# apu_mega_shield.net
KiCad netlist of a schematic drawn in EAGLE
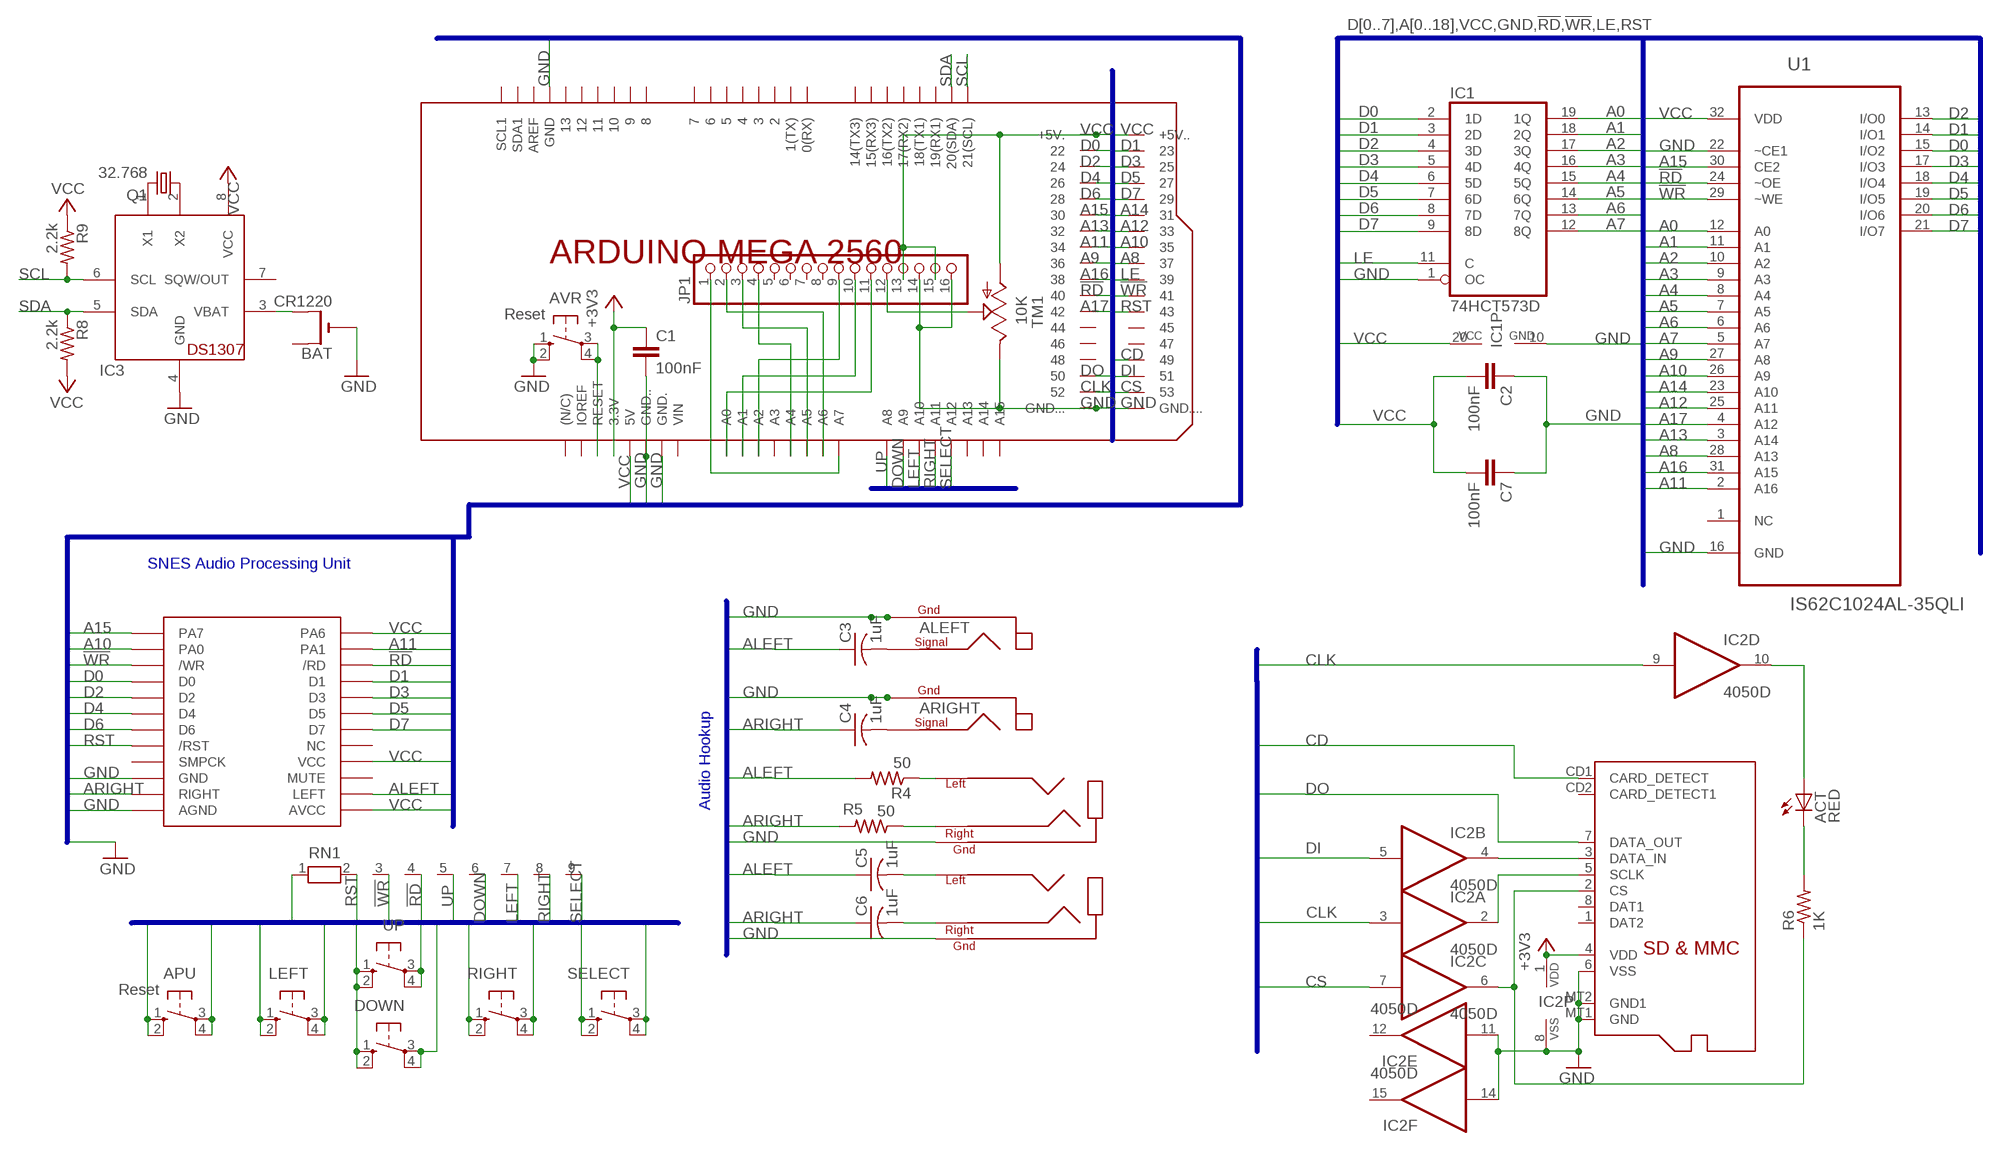
[diagram p0: schematic, sheet 1]

(export (version "E")
  (design (tool "Eeschema 10.0.6"))
  (components
    (comp (ref "ACT")
      (value "RED")
      (footprint "eagle-import:CHIP-LED0805")
      (libsource (lib "eagle-import") (part "LEDCHIP-LED0805"))
    )
    (comp (ref "APU")
      (value "Reset")
      (footprint "eagle-import:B3F-10XX")
      (libsource (lib "eagle-import") (part "10-XX"))
    )
    (comp (ref "AVR")
      (value "Reset")
      (footprint "eagle-import:B3F-10XX")
      (libsource (lib "eagle-import") (part "10-XX"))
    )
    (comp (ref "BAT")
      (value "CR1220")
      (footprint "eagle-import:CR1220-THM")
      (libsource (lib "eagle-import") (part "CR1220THM"))
    )
    (comp (ref "C1")
      (value "100nF")
      (footprint "eagle-import:C0603")
      (libsource (lib "eagle-import") (part "C-EUC0603"))
    )
    (comp (ref "C2")
      (value "100nF")
      (footprint "eagle-import:C0603")
      (libsource (lib "eagle-import") (part "C-EUC0603"))
    )
    (comp (ref "C3")
      (value "1uF")
      (footprint "eagle-import:C025-025X050")
      (libsource (lib "eagle-import") (part "C-US025-025X050"))
    )
    (comp (ref "C4")
      (value "1uF")
      (footprint "eagle-import:C025-025X050")
      (libsource (lib "eagle-import") (part "C-US025-025X050"))
    )
    (comp (ref "C5")
      (value "1uF")
      (footprint "eagle-import:C025-025X050")
      (libsource (lib "eagle-import") (part "C-US025-025X050"))
    )
    (comp (ref "C6")
      (value "1uF")
      (footprint "eagle-import:C025-025X050")
      (libsource (lib "eagle-import") (part "C-US025-025X050"))
    )
    (comp (ref "C7")
      (value "100nF")
      (footprint "eagle-import:C0603")
      (libsource (lib "eagle-import") (part "C-EUC0603"))
    )
    (comp (ref "DOWN")
      (value "10-XX")
      (footprint "eagle-import:B3F-10XX")
      (libsource (lib "eagle-import") (part "10-XX"))
    )
    (comp (ref "IC1")
      (value "74HCT573D")
      (footprint "eagle-import:SO20W")
      (libsource (lib "eagle-import") (part "74573DHCT"))
    )
    (comp (ref "IC2")
      (value "4050D")
      (footprint "eagle-import:SO16")
      (libsource (lib "eagle-import") (part "4050D"))
    )
    (comp (ref "IC3")
      (value "DS1307")
      (footprint "eagle-import:DIL08")
      (libsource (lib "eagle-import") (part "DS1307"))
    )
    (comp (ref "JP1")
      (value "PINHD-1X16")
      (footprint "eagle-import:1X16")
      (libsource (lib "eagle-import") (part "PINHD-1X16"))
    )
    (comp (ref "LEFT")
      (value "10-XX")
      (footprint "eagle-import:B3F-10XX")
      (libsource (lib "eagle-import") (part "10-XX"))
    )
    (comp (ref "Q1")
      (value "32.768")
      (footprint "eagle-import:TC38H")
      (libsource (lib "eagle-import") (part "CRYTALTC38H"))
    )
    (comp (ref "R4")
      (value "50")
      (footprint "eagle-import:0207_10")
      (libsource (lib "eagle-import") (part "rcl_R-US_0207/10"))
    )
    (comp (ref "R5")
      (value "50")
      (footprint "eagle-import:0207_10")
      (libsource (lib "eagle-import") (part "rcl_R-US_0207/10"))
    )
    (comp (ref "R6")
      (value "1K")
      (footprint "eagle-import:R0805")
      (libsource (lib "eagle-import") (part "R-US_R0805"))
    )
    (comp (ref "R8")
      (value "2.2k")
      (footprint "eagle-import:0207_10")
      (libsource (lib "eagle-import") (part "R-US_0207/10"))
    )
    (comp (ref "R9")
      (value "2.2k")
      (footprint "eagle-import:0207_10")
      (libsource (lib "eagle-import") (part "R-US_0207/10"))
    )
    (comp (ref "RIGHT")
      (value "10-XX")
      (footprint "eagle-import:B3F-10XX")
      (libsource (lib "eagle-import") (part "10-XX"))
    )
    (comp (ref "RN1")
      (value "RN08")
      (footprint "eagle-import:RN-9")
      (libsource (lib "eagle-import") (part "RN08"))
    )
    (comp (ref "SELECT")
      (value "10-XX")
      (footprint "eagle-import:B3F-10XX")
      (libsource (lib "eagle-import") (part "10-XX"))
    )
    (comp (ref "TM1")
      (value "10K")
      (footprint "eagle-import:CA6H")
      (libsource (lib "eagle-import") (part "TRIM_US-CA6H"))
    )
    (comp (ref "U$1")
      (value "APU")
      (footprint "eagle-import:APU")
      (libsource (lib "eagle-import") (part "APU"))
    )
    (comp (ref "U$2")
      (value "HEADPHONE")
      (footprint "eagle-import:SJ1-3533N")
      (libsource (lib "eagle-import") (part "HEADPHONE"))
    )
    (comp (ref "U$3")
      (value "HEADPHONE")
      (footprint "eagle-import:SJ1-3533N")
      (libsource (lib "eagle-import") (part "HEADPHONE"))
    )
    (comp (ref "U$4")
      (value "RCA")
      (footprint "eagle-import:RCJ-01X")
      (libsource (lib "eagle-import") (part "RCA"))
    )
    (comp (ref "U$5")
      (value "RCA")
      (footprint "eagle-import:RCJ-01X")
      (libsource (lib "eagle-import") (part "RCA"))
    )
    (comp (ref "U$6")
      (value "ARDUINO_MEGA_2560_LITENO_LABELS")
      (footprint "eagle-import:ARDUINO_MEGA2560_LITE_NO_LABELS")
      (libsource (lib "eagle-import") (part "ARDUINO_MEGA_2560_LITENO_LABELS"))
    )
    (comp (ref "U1")
      (value "IS62C1024AL-35QLI")
      (footprint "eagle-import:SOIC127P1412X305-32N")
      (libsource (lib "eagle-import") (part "IS62C1024AL-35QLI"))
    )
    (comp (ref "UP")
      (value "10-XX")
      (footprint "eagle-import:B3F-10XX")
      (libsource (lib "eagle-import") (part "10-XX"))
    )
    (comp (ref "X1")
      (value "MICROSD")
      (footprint "eagle-import:MICROSD")
      (libsource (lib "eagle-import") (part "MICROSD"))
    )
  )
  (nets
    (net (code "1") (name "+3V3") (class "Default")
      (node (ref "C1") (pin "1") (pinfunction "1_1") (pintype "passive"))
      (node (ref "IC2") (pin "1") (pinfunction "VDD_1") (pintype "power_in"))
      (node (ref "U$6") (pin "3.3V") (pinfunction "3.3V_3.3V") (pintype "bidirectional"))
      (node (ref "X1") (pin "4") (pinfunction "VDD_4") (pintype "power_in"))
    )
    (net (code "2") (name "/A0") (class "Default")
      (node (ref "IC1") (pin "19") (pinfunction "1Q_19") (pintype "tri_state"))
      (node (ref "U1") (pin "12") (pinfunction "A0_12") (pintype "input"))
    )
    (net (code "3") (name "/A1") (class "Default")
      (node (ref "IC1") (pin "18") (pinfunction "2Q_18") (pintype "tri_state"))
      (node (ref "U1") (pin "11") (pinfunction "A1_11") (pintype "input"))
    )
    (net (code "4") (name "/A2") (class "Default")
      (node (ref "IC1") (pin "17") (pinfunction "3Q_17") (pintype "tri_state"))
      (node (ref "U1") (pin "10") (pinfunction "A2_10") (pintype "input"))
    )
    (net (code "5") (name "/A3") (class "Default")
      (node (ref "IC1") (pin "16") (pinfunction "4Q_16") (pintype "tri_state"))
      (node (ref "U1") (pin "9") (pinfunction "A3_9") (pintype "input"))
    )
    (net (code "6") (name "/A4") (class "Default")
      (node (ref "IC1") (pin "15") (pinfunction "5Q_15") (pintype "tri_state"))
      (node (ref "U1") (pin "8") (pinfunction "A4_8") (pintype "input"))
    )
    (net (code "7") (name "/A5") (class "Default")
      (node (ref "IC1") (pin "14") (pinfunction "6Q_14") (pintype "tri_state"))
      (node (ref "U1") (pin "7") (pinfunction "A5_7") (pintype "input"))
    )
    (net (code "8") (name "/A6") (class "Default")
      (node (ref "IC1") (pin "13") (pinfunction "7Q_13") (pintype "tri_state"))
      (node (ref "U1") (pin "6") (pinfunction "A6_6") (pintype "input"))
    )
    (net (code "9") (name "/A7") (class "Default")
      (node (ref "IC1") (pin "12") (pinfunction "8Q_12") (pintype "tri_state"))
      (node (ref "U1") (pin "5") (pinfunction "A7_5") (pintype "input"))
    )
    (net (code "10") (name "/A8") (class "Default")
      (node (ref "U$6") (pin "37") (pinfunction "37_37") (pintype "bidirectional"))
      (node (ref "U1") (pin "28") (pinfunction "A13_28") (pintype "input"))
    )
    (net (code "11") (name "/A9") (class "Default")
      (node (ref "U$6") (pin "36") (pinfunction "36_36") (pintype "bidirectional"))
      (node (ref "U1") (pin "27") (pinfunction "A8_27") (pintype "input"))
    )
    (net (code "12") (name "/A10") (class "Default")
      (node (ref "U$1") (pin "P$3") (pinfunction "PA0_P$3") (pintype "bidirectional"))
      (node (ref "U$6") (pin "35") (pinfunction "35_35") (pintype "bidirectional"))
      (node (ref "U1") (pin "26") (pinfunction "A9_26") (pintype "input"))
    )
    (net (code "13") (name "/A11") (class "Default")
      (node (ref "U$1") (pin "P$4") (pinfunction "PA1_P$4") (pintype "bidirectional"))
      (node (ref "U$6") (pin "34") (pinfunction "34_34") (pintype "bidirectional"))
      (node (ref "U1") (pin "2") (pinfunction "A16_2") (pintype "input"))
    )
    (net (code "14") (name "/A12") (class "Default")
      (node (ref "U$6") (pin "33") (pinfunction "33_33") (pintype "bidirectional"))
      (node (ref "U1") (pin "25") (pinfunction "A11_25") (pintype "input"))
    )
    (net (code "15") (name "/A13") (class "Default")
      (node (ref "U$6") (pin "32") (pinfunction "32_32") (pintype "bidirectional"))
      (node (ref "U1") (pin "3") (pinfunction "A14_3") (pintype "input"))
    )
    (net (code "16") (name "/A14") (class "Default")
      (node (ref "U$6") (pin "31") (pinfunction "31_31") (pintype "bidirectional"))
      (node (ref "U1") (pin "23") (pinfunction "A10_23") (pintype "input"))
    )
    (net (code "17") (name "/A15") (class "Default")
      (node (ref "U$1") (pin "P$1") (pinfunction "PA7_P$1") (pintype "bidirectional"))
      (node (ref "U$6") (pin "30") (pinfunction "30_30") (pintype "bidirectional"))
      (node (ref "U1") (pin "30") (pinfunction "CE2_30") (pintype "input"))
    )
    (net (code "18") (name "/A16") (class "Default")
      (node (ref "U$6") (pin "38") (pinfunction "38_38") (pintype "bidirectional"))
      (node (ref "U1") (pin "31") (pinfunction "A15_31") (pintype "input"))
    )
    (net (code "19") (name "/A17") (class "Default")
      (node (ref "U$6") (pin "42") (pinfunction "42_42") (pintype "bidirectional"))
      (node (ref "U1") (pin "4") (pinfunction "A12_4") (pintype "input"))
    )
    (net (code "20") (name "/ALEFT") (class "Default")
      (node (ref "C3") (pin "1") (pinfunction "1_1") (pintype "passive"))
      (node (ref "C5") (pin "1") (pinfunction "1_1") (pintype "passive"))
      (node (ref "R4") (pin "2") (pinfunction "2_2") (pintype "passive"))
      (node (ref "U$1") (pin "P$22") (pinfunction "LEFT_P$22") (pintype "bidirectional"))
    )
    (net (code "21") (name "/ARIGHT") (class "Default")
      (node (ref "C4") (pin "1") (pinfunction "1_1") (pintype "passive"))
      (node (ref "C6") (pin "1") (pinfunction "1_1") (pintype "passive"))
      (node (ref "R5") (pin "2") (pinfunction "2_2") (pintype "passive"))
      (node (ref "U$1") (pin "P$21") (pinfunction "RIGHT_P$21") (pintype "bidirectional"))
    )
    (net (code "22") (name "/CD") (class "Default")
      (node (ref "U$6") (pin "49") (pinfunction "49_49") (pintype "bidirectional"))
      (node (ref "X1") (pin "CD1") (pinfunction "CARD_DETECT_CD1") (pintype "passive"))
    )
    (net (code "23") (name "/CLK") (class "Default")
      (node (ref "IC2") (pin "3") (pinfunction "I_3") (pintype "input"))
      (node (ref "IC2") (pin "9") (pinfunction "I_9") (pintype "input"))
      (node (ref "U$6") (pin "52") (pinfunction "52_52") (pintype "bidirectional"))
    )
    (net (code "24") (name "/CS") (class "Default")
      (node (ref "IC2") (pin "7") (pinfunction "I_7") (pintype "input"))
      (node (ref "U$6") (pin "53") (pinfunction "53_53") (pintype "bidirectional"))
    )
    (net (code "25") (name "/D0") (class "Default")
      (node (ref "IC1") (pin "2") (pinfunction "1D_2") (pintype "input"))
      (node (ref "U$1") (pin "P$7") (pinfunction "D0_P$7") (pintype "bidirectional"))
      (node (ref "U$6") (pin "22") (pinfunction "22_22") (pintype "bidirectional"))
      (node (ref "U1") (pin "15") (pinfunction "I/O2_15") (pintype "bidirectional"))
    )
    (net (code "26") (name "/D1") (class "Default")
      (node (ref "IC1") (pin "3") (pinfunction "2D_3") (pintype "input"))
      (node (ref "U$1") (pin "P$8") (pinfunction "D1_P$8") (pintype "bidirectional"))
      (node (ref "U$6") (pin "23") (pinfunction "23_23") (pintype "bidirectional"))
      (node (ref "U1") (pin "14") (pinfunction "I/O1_14") (pintype "bidirectional"))
    )
    (net (code "27") (name "/D2") (class "Default")
      (node (ref "IC1") (pin "4") (pinfunction "3D_4") (pintype "input"))
      (node (ref "U$1") (pin "P$9") (pinfunction "D2_P$9") (pintype "bidirectional"))
      (node (ref "U$6") (pin "24") (pinfunction "24_24") (pintype "bidirectional"))
      (node (ref "U1") (pin "13") (pinfunction "I/O0_13") (pintype "bidirectional"))
    )
    (net (code "28") (name "/D3") (class "Default")
      (node (ref "IC1") (pin "5") (pinfunction "4D_5") (pintype "input"))
      (node (ref "U$1") (pin "P$10") (pinfunction "D3_P$10") (pintype "bidirectional"))
      (node (ref "U$6") (pin "25") (pinfunction "25_25") (pintype "bidirectional"))
      (node (ref "U1") (pin "17") (pinfunction "I/O3_17") (pintype "bidirectional"))
    )
    (net (code "29") (name "/D4") (class "Default")
      (node (ref "IC1") (pin "6") (pinfunction "5D_6") (pintype "input"))
      (node (ref "U$1") (pin "P$11") (pinfunction "D4_P$11") (pintype "bidirectional"))
      (node (ref "U$6") (pin "26") (pinfunction "26_26") (pintype "bidirectional"))
      (node (ref "U1") (pin "18") (pinfunction "I/O4_18") (pintype "bidirectional"))
    )
    (net (code "30") (name "/D5") (class "Default")
      (node (ref "IC1") (pin "7") (pinfunction "6D_7") (pintype "input"))
      (node (ref "U$1") (pin "P$12") (pinfunction "D5_P$12") (pintype "bidirectional"))
      (node (ref "U$6") (pin "27") (pinfunction "27_27") (pintype "bidirectional"))
      (node (ref "U1") (pin "19") (pinfunction "I/O5_19") (pintype "bidirectional"))
    )
    (net (code "31") (name "/D6") (class "Default")
      (node (ref "IC1") (pin "8") (pinfunction "7D_8") (pintype "input"))
      (node (ref "U$1") (pin "P$13") (pinfunction "D6_P$13") (pintype "bidirectional"))
      (node (ref "U$6") (pin "28") (pinfunction "28_28") (pintype "bidirectional"))
      (node (ref "U1") (pin "20") (pinfunction "I/O6_20") (pintype "bidirectional"))
    )
    (net (code "32") (name "/D7") (class "Default")
      (node (ref "IC1") (pin "9") (pinfunction "8D_9") (pintype "input"))
      (node (ref "U$1") (pin "P$14") (pinfunction "D7_P$14") (pintype "bidirectional"))
      (node (ref "U$6") (pin "29") (pinfunction "29_29") (pintype "bidirectional"))
      (node (ref "U1") (pin "21") (pinfunction "I/O7_21") (pintype "bidirectional"))
    )
    (net (code "33") (name "/DI") (class "Default")
      (node (ref "IC2") (pin "5") (pinfunction "I_5") (pintype "input"))
      (node (ref "U$6") (pin "51") (pinfunction "51_51") (pintype "bidirectional"))
    )
    (net (code "34") (name "/DO") (class "Default")
      (node (ref "U$6") (pin "50") (pinfunction "50_50") (pintype "bidirectional"))
      (node (ref "X1") (pin "7") (pinfunction "DATA_OUT_7") (pintype "output"))
    )
    (net (code "35") (name "/DOWN") (class "Default")
      (node (ref "DOWN") (pin "3") (pinfunction "P_3") (pintype "passive"))
      (node (ref "DOWN") (pin "4") (pinfunction "P1_4") (pintype "passive"))
      (node (ref "RN1") (pin "6") (pinfunction "6_6") (pintype "passive"))
      (node (ref "U$6") (pin "A9") (pinfunction "A9_A9") (pintype "bidirectional"))
    )
    (net (code "36") (name "/LE") (class "Default")
      (node (ref "IC1") (pin "11") (pinfunction "C_11") (pintype "input"))
      (node (ref "U$6") (pin "39") (pinfunction "39_39") (pintype "bidirectional"))
    )
    (net (code "37") (name "/LEFT") (class "Default")
      (node (ref "LEFT") (pin "3") (pinfunction "P_3") (pintype "passive"))
      (node (ref "LEFT") (pin "4") (pinfunction "P1_4") (pintype "passive"))
      (node (ref "RN1") (pin "7") (pinfunction "7_7") (pintype "passive"))
      (node (ref "U$6") (pin "A10") (pinfunction "A10_A10") (pintype "bidirectional"))
    )
    (net (code "38") (name "/RIGHT") (class "Default")
      (node (ref "RIGHT") (pin "3") (pinfunction "P_3") (pintype "passive"))
      (node (ref "RIGHT") (pin "4") (pinfunction "P1_4") (pintype "passive"))
      (node (ref "RN1") (pin "8") (pinfunction "8_8") (pintype "passive"))
      (node (ref "U$6") (pin "A11") (pinfunction "A11_A11") (pintype "bidirectional"))
    )
    (net (code "39") (name "/RST") (class "Default")
      (node (ref "APU") (pin "3") (pinfunction "P_3") (pintype "passive"))
      (node (ref "APU") (pin "4") (pinfunction "P1_4") (pintype "passive"))
      (node (ref "RN1") (pin "2") (pinfunction "2_2") (pintype "passive"))
      (node (ref "U$1") (pin "P$15") (pinfunction "/RST_P$15") (pintype "bidirectional"))
      (node (ref "U$6") (pin "43") (pinfunction "43_43") (pintype "bidirectional"))
    )
    (net (code "40") (name "/SCL") (class "Default")
      (node (ref "IC3") (pin "6") (pinfunction "SCL_6") (pintype "bidirectional"))
      (node (ref "R9") (pin "2") (pinfunction "2_2") (pintype "passive"))
      (node (ref "U$6") (pin "21") (pinfunction "21(SCL)_21") (pintype "bidirectional"))
    )
    (net (code "41") (name "/SDA") (class "Default")
      (node (ref "IC3") (pin "5") (pinfunction "SDA_5") (pintype "bidirectional"))
      (node (ref "R8") (pin "1") (pinfunction "1_1") (pintype "passive"))
      (node (ref "U$6") (pin "20") (pinfunction "20(SDA)_20") (pintype "bidirectional"))
    )
    (net (code "42") (name "/SELECT") (class "Default")
      (node (ref "RN1") (pin "9") (pinfunction "9_9") (pintype "passive"))
      (node (ref "SELECT") (pin "3") (pinfunction "P_3") (pintype "passive"))
      (node (ref "SELECT") (pin "4") (pinfunction "P1_4") (pintype "passive"))
      (node (ref "U$6") (pin "A12") (pinfunction "A12_A12") (pintype "bidirectional"))
    )
    (net (code "43") (name "/UP") (class "Default")
      (node (ref "RN1") (pin "5") (pinfunction "5_5") (pintype "passive"))
      (node (ref "U$6") (pin "A8") (pinfunction "A8_A8") (pintype "bidirectional"))
      (node (ref "UP") (pin "3") (pinfunction "P_3") (pintype "passive"))
      (node (ref "UP") (pin "4") (pinfunction "P1_4") (pintype "passive"))
    )
    (net (code "46") (name "/~{RD}") (class "Default")
      (node (ref "RN1") (pin "4") (pinfunction "4_4") (pintype "passive"))
      (node (ref "U$1") (pin "P$6") (pinfunction "/RD_P$6") (pintype "bidirectional"))
      (node (ref "U$6") (pin "40") (pinfunction "40_40") (pintype "bidirectional"))
      (node (ref "U1") (pin "24") (pinfunction "~{OE}_24") (pintype "input"))
    )
    (net (code "47") (name "/~{WR}") (class "Default")
      (node (ref "RN1") (pin "3") (pinfunction "3_3") (pintype "passive"))
      (node (ref "U$1") (pin "P$5") (pinfunction "/WR_P$5") (pintype "bidirectional"))
      (node (ref "U$6") (pin "41") (pinfunction "41_41") (pintype "bidirectional"))
      (node (ref "U1") (pin "29") (pinfunction "~{WE}_29") (pintype "input"))
    )
    (net (code "48") (name "GND") (class "Default")
      (node (ref "APU") (pin "1") (pinfunction "S_1") (pintype "passive"))
      (node (ref "APU") (pin "2") (pinfunction "S1_2") (pintype "passive"))
      (node (ref "AVR") (pin "1") (pinfunction "S_1") (pintype "passive"))
      (node (ref "AVR") (pin "2") (pinfunction "S1_2") (pintype "passive"))
      (node (ref "BAT") (pin "-") (pinfunction "-_-") (pintype "passive"))
      (node (ref "C1") (pin "2") (pinfunction "2_2") (pintype "passive"))
      (node (ref "C2") (pin "1") (pinfunction "1_1") (pintype "passive"))
      (node (ref "C7") (pin "1") (pinfunction "1_1") (pintype "passive"))
      (node (ref "DOWN") (pin "1") (pinfunction "S_1") (pintype "passive"))
      (node (ref "DOWN") (pin "2") (pinfunction "S1_2") (pintype "passive"))
      (node (ref "IC1") (pin "1") (pinfunction "OC_1") (pintype "input"))
      (node (ref "IC1") (pin "10") (pinfunction "GND_10") (pintype "power_in"))
      (node (ref "IC2") (pin "11") (pinfunction "I_11") (pintype "input"))
      (node (ref "IC2") (pin "14") (pinfunction "I_14") (pintype "input"))
      (node (ref "IC2") (pin "8") (pinfunction "VSS_8") (pintype "power_in"))
      (node (ref "IC3") (pin "4") (pinfunction "GND_4") (pintype "power_in"))
      (node (ref "JP1") (pin "14") (pinfunction "14_14") (pintype "passive"))
      (node (ref "JP1") (pin "16") (pinfunction "16_16") (pintype "passive"))
      (node (ref "LEFT") (pin "1") (pinfunction "S_1") (pintype "passive"))
      (node (ref "LEFT") (pin "2") (pinfunction "S1_2") (pintype "passive"))
      (node (ref "RIGHT") (pin "1") (pinfunction "S_1") (pintype "passive"))
      (node (ref "RIGHT") (pin "2") (pinfunction "S1_2") (pintype "passive"))
      (node (ref "SELECT") (pin "1") (pinfunction "S_1") (pintype "passive"))
      (node (ref "SELECT") (pin "2") (pinfunction "S1_2") (pintype "passive"))
      (node (ref "TM1") (pin "E") (pinfunction "E_E") (pintype "passive"))
      (node (ref "U$1") (pin "P$19") (pinfunction "GND_P$19") (pintype "bidirectional"))
      (node (ref "U$1") (pin "P$23") (pinfunction "AGND_P$23") (pintype "bidirectional"))
      (node (ref "U$2") (pin "GND") (pinfunction "GND_GND") (pintype "bidirectional"))
      (node (ref "U$3") (pin "GND") (pinfunction "GND_GND") (pintype "bidirectional"))
      (node (ref "U$4") (pin "PGND1") (pinfunction "PGND1_PGND1") (pintype "bidirectional"))
      (node (ref "U$4") (pin "PGND2") (pinfunction "PGND1_PGND2") (pintype "bidirectional"))
      (node (ref "U$4") (pin "PGND3") (pinfunction "PGND1_PGND3") (pintype "bidirectional"))
      (node (ref "U$5") (pin "PGND1") (pinfunction "PGND1_PGND1") (pintype "bidirectional"))
      (node (ref "U$5") (pin "PGND2") (pinfunction "PGND1_PGND2") (pintype "bidirectional"))
      (node (ref "U$5") (pin "PGND3") (pinfunction "PGND1_PGND3") (pintype "bidirectional"))
      (node (ref "U$6") (pin "GND") (pinfunction "GND_GND") (pintype "bidirectional"))
      (node (ref "U$6") (pin "GND.") (pinfunction "GND._GND.") (pintype "bidirectional"))
      (node (ref "U$6") (pin "GND..") (pinfunction "GND.._GND..") (pintype "bidirectional"))
      (node (ref "U$6") (pin "GND...") (pinfunction "GND..._GND...") (pintype "bidirectional"))
      (node (ref "U$6") (pin "GND....") (pinfunction "GND...._GND....") (pintype "bidirectional"))
      (node (ref "U1") (pin "16") (pinfunction "GND_16") (pintype "passive"))
      (node (ref "U1") (pin "22") (pinfunction "~{CE1}_22") (pintype "input"))
      (node (ref "UP") (pin "1") (pinfunction "S_1") (pintype "passive"))
      (node (ref "UP") (pin "2") (pinfunction "S1_2") (pintype "passive"))
      (node (ref "X1") (pin "6") (pinfunction "VSS_6") (pintype "power_in"))
      (node (ref "X1") (pin "MT1") (pinfunction "GND_MT1") (pintype "power_in"))
      (node (ref "X1") (pin "MT2") (pinfunction "GND1_MT2") (pintype "power_in"))
    )
    (net (code "49") (name "Net-(ACT-PadC)") (class "Default")
      (node (ref "ACT") (pin "C") (pinfunction "C_C") (pintype "passive"))
      (node (ref "R6") (pin "2") (pinfunction "2_2") (pintype "passive"))
    )
    (net (code "50") (name "Net-(AVR-P)") (class "Default")
      (node (ref "AVR") (pin "3") (pinfunction "P_3") (pintype "passive"))
      (node (ref "AVR") (pin "4") (pinfunction "P1_4") (pintype "passive"))
      (node (ref "U$6") (pin "RESET") (pinfunction "RESET_RESET") (pintype "bidirectional"))
    )
    (net (code "51") (name "Net-(BAT-+1)") (class "Default")
      (node (ref "BAT") (pin "+2") (pinfunction "+1_+2") (pintype "passive"))
      (node (ref "IC3") (pin "3") (pinfunction "VBAT_3") (pintype "power_in"))
    )
    (net (code "52") (name "Net-(C3-Pad2)") (class "Default")
      (node (ref "C3") (pin "2") (pinfunction "2_2") (pintype "passive"))
      (node (ref "U$4") (pin "PSIG") (pinfunction "PSIG_PSIG") (pintype "bidirectional"))
    )
    (net (code "53") (name "Net-(C4-Pad2)") (class "Default")
      (node (ref "C4") (pin "2") (pinfunction "2_2") (pintype "passive"))
      (node (ref "U$5") (pin "PSIG") (pinfunction "PSIG_PSIG") (pintype "bidirectional"))
    )
    (net (code "54") (name "Net-(C5-Pad2)") (class "Default")
      (node (ref "C5") (pin "2") (pinfunction "2_2") (pintype "passive"))
      (node (ref "U$3") (pin "LEFT") (pinfunction "LEFT_LEFT") (pintype "bidirectional"))
    )
    (net (code "55") (name "Net-(C6-Pad2)") (class "Default")
      (node (ref "C6") (pin "2") (pinfunction "2_2") (pintype "passive"))
      (node (ref "U$3") (pin "RIGHT") (pinfunction "RIGHT_RIGHT") (pintype "bidirectional"))
    )
    (net (code "56") (name "Net-(IC2A-O)") (class "Default")
      (node (ref "IC2") (pin "2") (pinfunction "O_2") (pintype "output"))
      (node (ref "X1") (pin "5") (pinfunction "SCLK_5") (pintype "input"))
    )
    (net (code "57") (name "Net-(IC2B-O)") (class "Default")
      (node (ref "IC2") (pin "4") (pinfunction "O_4") (pintype "output"))
      (node (ref "X1") (pin "3") (pinfunction "DATA_IN_3") (pintype "input"))
    )
    (net (code "58") (name "Net-(IC2C-O)") (class "Default")
      (node (ref "IC2") (pin "6") (pinfunction "O_6") (pintype "output"))
      (node (ref "R6") (pin "1") (pinfunction "1_1") (pintype "passive"))
      (node (ref "X1") (pin "2") (pinfunction "CS_2") (pintype "input"))
    )
    (net (code "59") (name "Net-(IC2D-O)") (class "Default")
      (node (ref "ACT") (pin "A") (pinfunction "A_A") (pintype "passive"))
      (node (ref "IC2") (pin "10") (pinfunction "O_10") (pintype "output"))
    )
    (net (code "60") (name "Net-(IC3-X1)") (class "Default")
      (node (ref "IC3") (pin "1") (pinfunction "X1_1") (pintype "passive"))
      (node (ref "Q1") (pin "2") (pinfunction "2_2") (pintype "passive"))
    )
    (net (code "61") (name "Net-(IC3-X2)") (class "Default")
      (node (ref "IC3") (pin "2") (pinfunction "X2_2") (pintype "passive"))
      (node (ref "Q1") (pin "1") (pinfunction "1_1") (pintype "passive"))
    )
    (net (code "62") (name "Net-(JP1-Pad1)") (class "Default")
      (node (ref "JP1") (pin "1") (pinfunction "1_1") (pintype "passive"))
      (node (ref "U$6") (pin "A7") (pinfunction "A7_A7") (pintype "bidirectional"))
    )
    (net (code "63") (name "Net-(JP1-Pad2)") (class "Default")
      (node (ref "JP1") (pin "2") (pinfunction "2_2") (pintype "passive"))
      (node (ref "U$6") (pin "A6") (pinfunction "A6_A6") (pintype "bidirectional"))
    )
    (net (code "64") (name "Net-(JP1-Pad3)") (class "Default")
      (node (ref "JP1") (pin "3") (pinfunction "3_3") (pintype "passive"))
      (node (ref "U$6") (pin "A5") (pinfunction "A5_A5") (pintype "bidirectional"))
    )
    (net (code "65") (name "Net-(JP1-Pad4)") (class "Default")
      (node (ref "JP1") (pin "4") (pinfunction "4_4") (pintype "passive"))
      (node (ref "U$6") (pin "A4") (pinfunction "A4_A4") (pintype "bidirectional"))
    )
    (net (code "66") (name "Net-(JP1-Pad9)") (class "Default")
      (node (ref "JP1") (pin "9") (pinfunction "9_9") (pintype "passive"))
      (node (ref "U$6") (pin "A2") (pinfunction "A2_A2") (pintype "bidirectional"))
    )
    (net (code "67") (name "Net-(JP1-Pad10)") (class "Default")
      (node (ref "JP1") (pin "10") (pinfunction "10_10") (pintype "passive"))
      (node (ref "U$6") (pin "A1") (pinfunction "A1_A1") (pintype "bidirectional"))
    )
    (net (code "68") (name "Net-(JP1-Pad11)") (class "Default")
      (node (ref "JP1") (pin "11") (pinfunction "11_11") (pintype "passive"))
      (node (ref "U$6") (pin "A0") (pinfunction "A0_A0") (pintype "bidirectional"))
    )
    (net (code "69") (name "Net-(JP1-Pad12)") (class "Default")
      (node (ref "JP1") (pin "12") (pinfunction "12_12") (pintype "passive"))
      (node (ref "TM1") (pin "S") (pinfunction "S_S") (pintype "passive"))
    )
    (net (code "70") (name "Net-(R4-Pad1)") (class "Default")
      (node (ref "R4") (pin "1") (pinfunction "1_1") (pintype "passive"))
      (node (ref "U$2") (pin "LEFT") (pinfunction "LEFT_LEFT") (pintype "bidirectional"))
    )
    (net (code "71") (name "Net-(R5-Pad1)") (class "Default")
      (node (ref "R5") (pin "1") (pinfunction "1_1") (pintype "passive"))
      (node (ref "U$2") (pin "RIGHT") (pinfunction "RIGHT_RIGHT") (pintype "bidirectional"))
    )
    (net (code "72") (name "VCC") (class "Default")
      (node (ref "C2") (pin "2") (pinfunction "2_2") (pintype "passive"))
      (node (ref "C7") (pin "2") (pinfunction "2_2") (pintype "passive"))
      (node (ref "IC1") (pin "20") (pinfunction "VCC_20") (pintype "power_in"))
      (node (ref "IC3") (pin "8") (pinfunction "VCC_8") (pintype "power_in"))
      (node (ref "JP1") (pin "13") (pinfunction "13_13") (pintype "passive"))
      (node (ref "JP1") (pin "15") (pinfunction "15_15") (pintype "passive"))
      (node (ref "R8") (pin "2") (pinfunction "2_2") (pintype "passive"))
      (node (ref "R9") (pin "1") (pinfunction "1_1") (pintype "passive"))
      (node (ref "RN1") (pin "1") (pinfunction "1_1") (pintype "passive"))
      (node (ref "TM1") (pin "A") (pinfunction "A_A") (pintype "passive"))
      (node (ref "U$1") (pin "P$18") (pinfunction "VCC_P$18") (pintype "bidirectional"))
      (node (ref "U$1") (pin "P$2") (pinfunction "PA6_P$2") (pintype "bidirectional"))
      (node (ref "U$1") (pin "P$24") (pinfunction "AVCC_P$24") (pintype "bidirectional"))
      (node (ref "U$6") (pin "5V") (pinfunction "5V_5V") (pintype "bidirectional"))
      (node (ref "U$6") (pin "5V.") (pinfunction "+5V._5V.") (pintype "bidirectional"))
      (node (ref "U$6") (pin "5V..") (pinfunction "+5V.._5V..") (pintype "bidirectional"))
      (node (ref "U1") (pin "32") (pinfunction "VDD_32") (pintype "power_in"))
    )
    (net (code "73") (name "unconnected-(BAT-+-Pad+1)") (class "Default")
      (node (ref "BAT") (pin "+1") (pinfunction "+_+1") (pintype "passive"))
    )
    (net (code "74") (name "unconnected-(IC2E-O-Pad12)") (class "Default")
      (node (ref "IC2") (pin "12") (pinfunction "O_12") (pintype "output"))
    )
    (net (code "75") (name "unconnected-(IC2F-O-Pad15)") (class "Default")
      (node (ref "IC2") (pin "15") (pinfunction "O_15") (pintype "output"))
    )
    (net (code "76") (name "unconnected-(IC3-SQW{slash}OUT-Pad7)") (class "Default")
      (node (ref "IC3") (pin "7") (pinfunction "SQW/OUT_7") (pintype "bidirectional"))
    )
    (net (code "77") (name "unconnected-(JP1-Pad5)") (class "Default")
      (node (ref "JP1") (pin "5") (pinfunction "5_5") (pintype "passive"))
    )
    (net (code "78") (name "unconnected-(JP1-Pad6)") (class "Default")
      (node (ref "JP1") (pin "6") (pinfunction "6_6") (pintype "passive"))
    )
    (net (code "79") (name "unconnected-(JP1-Pad7)") (class "Default")
      (node (ref "JP1") (pin "7") (pinfunction "7_7") (pintype "passive"))
    )
    (net (code "80") (name "unconnected-(JP1-Pad8)") (class "Default")
      (node (ref "JP1") (pin "8") (pinfunction "8_8") (pintype "passive"))
    )
    (net (code "81") (name "unconnected-(U$1-MUTE-PadP$20)") (class "Default")
      (node (ref "U$1") (pin "P$20") (pinfunction "MUTE_P$20") (pintype "bidirectional"))
    )
    (net (code "82") (name "unconnected-(U$1-NC-PadP$16)") (class "Default")
      (node (ref "U$1") (pin "P$16") (pinfunction "NC_P$16") (pintype "bidirectional"))
    )
    (net (code "83") (name "unconnected-(U$1-SMPCK-PadP$17)") (class "Default")
      (node (ref "U$1") (pin "P$17") (pinfunction "SMPCK_P$17") (pintype "bidirectional"))
    )
    (net (code "84") (name "unconnected-(U$6-(N{slash}C)-PadN{slash}C)") (class "Default")
      (node (ref "U$6") (pin "N/C") (pinfunction "(N/C)_N/C") (pintype "bidirectional"))
    )
    (net (code "85") (name "unconnected-(U$6-0(RX)-Pad0)") (class "Default")
      (node (ref "U$6") (pin "0") (pinfunction "0(RX)_0") (pintype "bidirectional"))
    )
    (net (code "86") (name "unconnected-(U$6-1(TX)-Pad1)") (class "Default")
      (node (ref "U$6") (pin "1") (pinfunction "1(TX)_1") (pintype "bidirectional"))
    )
    (net (code "87") (name "unconnected-(U$6-14(TX3)-Pad14)") (class "Default")
      (node (ref "U$6") (pin "14") (pinfunction "14(TX3)_14") (pintype "bidirectional"))
    )
    (net (code "88") (name "unconnected-(U$6-15(RX3)-Pad15)") (class "Default")
      (node (ref "U$6") (pin "15") (pinfunction "15(RX3)_15") (pintype "bidirectional"))
    )
    (net (code "89") (name "unconnected-(U$6-16(TX2)-Pad16)") (class "Default")
      (node (ref "U$6") (pin "16") (pinfunction "16(TX2)_16") (pintype "bidirectional"))
    )
    (net (code "90") (name "unconnected-(U$6-17(RX2)-Pad17)") (class "Default")
      (node (ref "U$6") (pin "17") (pinfunction "17(RX2)_17") (pintype "bidirectional"))
    )
    (net (code "91") (name "unconnected-(U$6-18(TX1)-Pad18)") (class "Default")
      (node (ref "U$6") (pin "18") (pinfunction "18(TX1)_18") (pintype "bidirectional"))
    )
    (net (code "92") (name "unconnected-(U$6-19(RX1)-Pad19)") (class "Default")
      (node (ref "U$6") (pin "19") (pinfunction "19(RX1)_19") (pintype "bidirectional"))
    )
    (net (code "93") (name "unconnected-(U$6-IOREF-PadI{slash}OREF)") (class "Default")
      (node (ref "U$6") (pin "I/OREF") (pinfunction "IOREF_I/OREF") (pintype "bidirectional"))
    )
    (net (code "94") (name "unconnected-(U$6-Pad2)") (class "Default")
      (node (ref "U$6") (pin "2") (pinfunction "2_2") (pintype "bidirectional"))
    )
    (net (code "95") (name "unconnected-(U$6-Pad3)") (class "Default")
      (node (ref "U$6") (pin "3") (pinfunction "3_3") (pintype "bidirectional"))
    )
    (net (code "96") (name "unconnected-(U$6-Pad4)") (class "Default")
      (node (ref "U$6") (pin "4") (pinfunction "4_4") (pintype "bidirectional"))
    )
    (net (code "97") (name "unconnected-(U$6-Pad5)") (class "Default")
      (node (ref "U$6") (pin "5") (pinfunction "5_5") (pintype "bidirectional"))
    )
    (net (code "98") (name "unconnected-(U$6-Pad6)") (class "Default")
      (node (ref "U$6") (pin "6") (pinfunction "6_6") (pintype "bidirectional"))
    )
    (net (code "99") (name "unconnected-(U$6-Pad7)") (class "Default")
      (node (ref "U$6") (pin "7") (pinfunction "7_7") (pintype "bidirectional"))
    )
    (net (code "100") (name "unconnected-(U$6-Pad8)") (class "Default")
      (node (ref "U$6") (pin "8") (pinfunction "8_8") (pintype "bidirectional"))
    )
    (net (code "101") (name "unconnected-(U$6-Pad9)") (class "Default")
      (node (ref "U$6") (pin "9") (pinfunction "9_9") (pintype "bidirectional"))
    )
    (net (code "102") (name "unconnected-(U$6-Pad10)") (class "Default")
      (node (ref "U$6") (pin "10") (pinfunction "10_10") (pintype "bidirectional"))
    )
    (net (code "103") (name "unconnected-(U$6-Pad11)") (class "Default")
      (node (ref "U$6") (pin "11") (pinfunction "11_11") (pintype "bidirectional"))
    )
    (net (code "104") (name "unconnected-(U$6-Pad12)") (class "Default")
      (node (ref "U$6") (pin "12") (pinfunction "12_12") (pintype "bidirectional"))
    )
    (net (code "105") (name "unconnected-(U$6-Pad13)") (class "Default")
      (node (ref "U$6") (pin "13") (pinfunction "13_13") (pintype "bidirectional"))
    )
    (net (code "106") (name "unconnected-(U$6-Pad44)") (class "Default")
      (node (ref "U$6") (pin "44") (pinfunction "44_44") (pintype "bidirectional"))
    )
    (net (code "107") (name "unconnected-(U$6-Pad45)") (class "Default")
      (node (ref "U$6") (pin "45") (pinfunction "45_45") (pintype "bidirectional"))
    )
    (net (code "108") (name "unconnected-(U$6-Pad46)") (class "Default")
      (node (ref "U$6") (pin "46") (pinfunction "46_46") (pintype "bidirectional"))
    )
    (net (code "109") (name "unconnected-(U$6-Pad47)") (class "Default")
      (node (ref "U$6") (pin "47") (pinfunction "47_47") (pintype "bidirectional"))
    )
    (net (code "110") (name "unconnected-(U$6-Pad48)") (class "Default")
      (node (ref "U$6") (pin "48") (pinfunction "48_48") (pintype "bidirectional"))
    )
    (net (code "111") (name "unconnected-(U$6-PadA3)") (class "Default")
      (node (ref "U$6") (pin "A3") (pinfunction "A3_A3") (pintype "bidirectional"))
    )
    (net (code "112") (name "unconnected-(U$6-PadA13)") (class "Default")
      (node (ref "U$6") (pin "A13") (pinfunction "A13_A13") (pintype "bidirectional"))
    )
    (net (code "113") (name "unconnected-(U$6-PadA14)") (class "Default")
      (node (ref "U$6") (pin "A14") (pinfunction "A14_A14") (pintype "bidirectional"))
    )
    (net (code "114") (name "unconnected-(U$6-PadA15)") (class "Default")
      (node (ref "U$6") (pin "A15") (pinfunction "A15_A15") (pintype "bidirectional"))
    )
    (net (code "115") (name "unconnected-(U$6-PadAREF)") (class "Default")
      (node (ref "U$6") (pin "AREF") (pinfunction "AREF_AREF") (pintype "bidirectional"))
    )
    (net (code "116") (name "unconnected-(U$6-PadSCL1)") (class "Default")
      (node (ref "U$6") (pin "SCL1") (pinfunction "SCL1_SCL1") (pintype "bidirectional"))
    )
    (net (code "117") (name "unconnected-(U$6-PadSDA1)") (class "Default")
      (node (ref "U$6") (pin "SDA1") (pinfunction "SDA1_SDA1") (pintype "bidirectional"))
    )
    (net (code "118") (name "unconnected-(U$6-PadVIN)") (class "Default")
      (node (ref "U$6") (pin "VIN") (pinfunction "VIN_VIN") (pintype "bidirectional"))
    )
    (net (code "119") (name "unconnected-(U1-NC-Pad1)") (class "Default")
      (node (ref "U1") (pin "1") (pinfunction "NC_1") (pintype "no_connect"))
    )
    (net (code "120") (name "unconnected-(X1-CARD_DETECT1-PadCD2)") (class "Default")
      (node (ref "X1") (pin "CD2") (pinfunction "CARD_DETECT1_CD2") (pintype "passive"))
    )
    (net (code "121") (name "unconnected-(X1-DAT1-Pad8)") (class "Default")
      (node (ref "X1") (pin "8") (pinfunction "DAT1_8") (pintype "bidirectional"))
    )
    (net (code "122") (name "unconnected-(X1-DAT2-Pad1)") (class "Default")
      (node (ref "X1") (pin "1") (pinfunction "DAT2_1") (pintype "bidirectional"))
    )
  )
)
